# power.net
KiCad netlist of a schematic drawn in Altium Designer
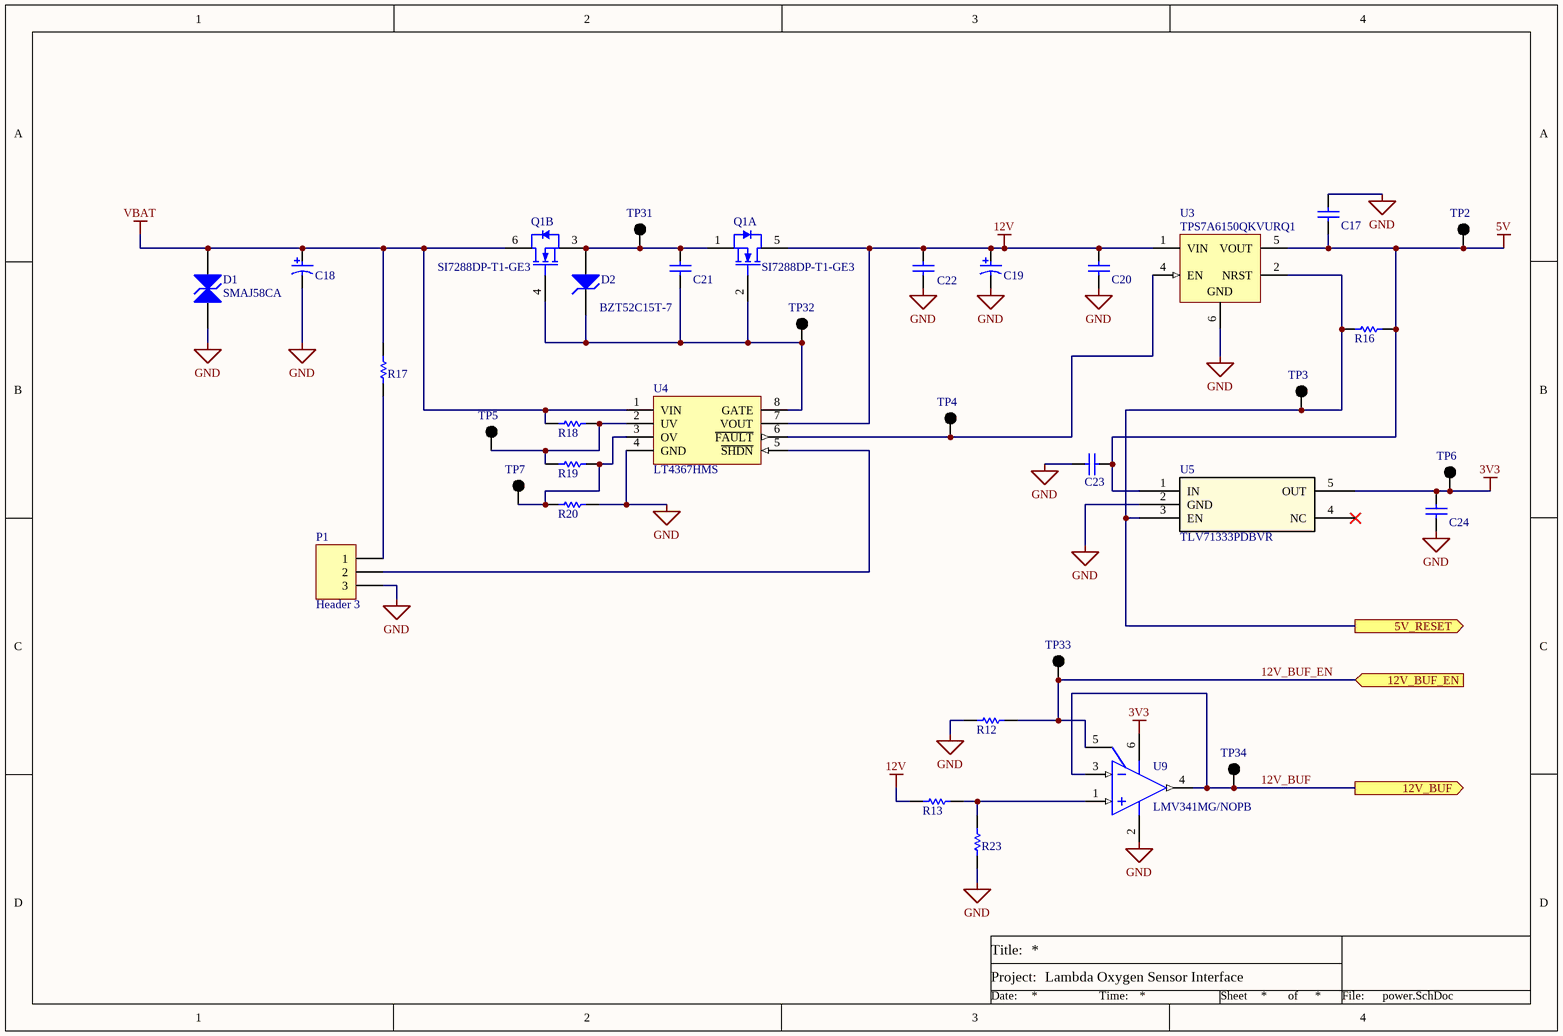
[diagram p0: power.SchDoc]

(export (version "E")
  (design (tool "Eeschema 10.0.6"))
  (components
    (comp (ref "C17")
      (value "Generic 0805 Capacitor")
      (footprint "0805")
      (libsource (lib "symbol_library") (part "C_0805"))
    )
    (comp (ref "C18")
      (value "Generic Electrolytic Capacitor")
      (footprint "NIC-UUX2A470MNL1GS_M")
      (description "Generic PCAP_10x10 Can Aluminum Electrolytic Capacitor")
      (libsource (lib "symbol_library") (part "C_can"))
    )
    (comp (ref "C19")
      (value "Generic Electrolytic Capacitor")
      (footprint "NIC-UUX2A470MNL1GS_M")
      (description "Generic PCAP_10x10 Can Aluminum Electrolytic Capacitor")
      (libsource (lib "symbol_library") (part "C_can"))
    )
    (comp (ref "C20")
      (value "Generic 0805 Capacitor")
      (footprint "0805")
      (libsource (lib "symbol_library") (part "C_0805"))
    )
    (comp (ref "C21")
      (value "Generic 0805 Capacitor")
      (footprint "0805")
      (libsource (lib "symbol_library") (part "C_0805"))
    )
    (comp (ref "C22")
      (value "Generic 0805 Capacitor")
      (footprint "0805")
      (libsource (lib "symbol_library") (part "C_0805"))
    )
    (comp (ref "C23")
      (value "Generic 0805 Capacitor")
      (footprint "0805")
      (libsource (lib "symbol_library") (part "C_0805"))
    )
    (comp (ref "C24")
      (value "Generic 0805 Capacitor")
      (footprint "0805")
      (libsource (lib "symbol_library") (part "C_0805"))
    )
    (comp (ref "D1")
      (value "SMAJ58CA")
      (footprint "VISH-DO-214AC-2_M")
      (fields
        (field (name "MANUFACTURER") "Vishay Semiconductor")
        (field (name "PARTNUMBER") "SMAJ58CA-E3/5A")
      )
      (libsource (lib "symbol_library") (part "SMAJ58CA"))
    )
    (comp (ref "D2")
      (value "BZT52C15T-7")
      (footprint "DIOD-SOD123-2_V")
      (description "Zener Diode 15V 300mW ±6% Surface Mount SOD-523")
      (fields (field (name "MANUFACTURER") "Diodes Inc") (field (name "PARTNUMBER") "BZT52C16-7-F"))
      (libsource (lib "symbol_library") (part "BZT52C15T"))
    )
    (comp (ref "P1")
      (value "Header 3")
      (footprint "HDR1X3")
      (description "Header, 3-Pin")
      (fields (field (name "PUBLISHER") "Altium Limited"))
      (libsource (lib "Miscellaneous Connectors") (part "Header 3"))
    )
    (comp (ref "Q1")
      (value "SI7288DP-T1-GE3")
      (footprint "VISH-POWERPAKSO-8_A_V")
      (description "Dual N-Channel (D-S) MOSFET, 40 V, 20 A, -55 to 150 degC, 8-Pin POWERPAKSO-8, RoHS, Tape and Reel")
      (fields (field (name "MANUFACTURER") "Vishay"))
      (libsource (lib "symbol_library") (part "SI7288DP"))
    )
    (comp (ref "R12")
      (value "Generic 0603 Resistor")
      (footprint "0603")
      (libsource (lib "symbol_library") (part "R_0603"))
    )
    (comp (ref "R13")
      (value "Generic 0603 Resistor")
      (footprint "0603")
      (libsource (lib "symbol_library") (part "R_0603"))
    )
    (comp (ref "R16")
      (value "Generic 0603 Resistor")
      (footprint "0603")
      (libsource (lib "symbol_library") (part "R_0603"))
    )
    (comp (ref "R17")
      (value "Generic 0603 Resistor")
      (footprint "0603")
      (libsource (lib "symbol_library") (part "R_0603"))
    )
    (comp (ref "R18")
      (value "Generic 0603 Resistor")
      (footprint "0603")
      (libsource (lib "symbol_library") (part "R_0603"))
    )
    (comp (ref "R19")
      (value "Generic 0603 Resistor")
      (footprint "0603")
      (libsource (lib "symbol_library") (part "R_0603"))
    )
    (comp (ref "R20")
      (value "Generic 0603 Resistor")
      (footprint "0603")
      (libsource (lib "symbol_library") (part "R_0603"))
    )
    (comp (ref "R23")
      (value "Generic 0603 Resistor")
      (footprint "0603")
      (libsource (lib "symbol_library") (part "R_0603"))
    )
    (comp (ref "TP2")
      (value "5001")
      (footprint "KSTN-5001")
      (description "Test Point, Black, 1-Pin THD, RoHS, Bulk")
      (fields (field (name "MANUFACTURER") "Keystone"))
      (libsource (lib "symbol_library") (part "TP5001"))
    )
    (comp (ref "TP3")
      (value "5001")
      (footprint "KSTN-5001")
      (description "Test Point, Black, 1-Pin THD, RoHS, Bulk")
      (fields (field (name "MANUFACTURER") "Keystone"))
      (libsource (lib "symbol_library") (part "TP5001"))
    )
    (comp (ref "TP4")
      (value "5001")
      (footprint "KSTN-5001")
      (description "Test Point, Black, 1-Pin THD, RoHS, Bulk")
      (fields (field (name "MANUFACTURER") "Keystone"))
      (libsource (lib "symbol_library") (part "TP5001"))
    )
    (comp (ref "TP5")
      (value "5001")
      (footprint "KSTN-5001")
      (description "Test Point, Black, 1-Pin THD, RoHS, Bulk")
      (fields (field (name "MANUFACTURER") "Keystone"))
      (libsource (lib "symbol_library") (part "TP5001"))
    )
    (comp (ref "TP6")
      (value "5001")
      (footprint "KSTN-5001")
      (description "Test Point, Black, 1-Pin THD, RoHS, Bulk")
      (fields (field (name "MANUFACTURER") "Keystone"))
      (libsource (lib "symbol_library") (part "TP5001"))
    )
    (comp (ref "TP7")
      (value "5001")
      (footprint "KSTN-5001")
      (description "Test Point, Black, 1-Pin THD, RoHS, Bulk")
      (fields (field (name "MANUFACTURER") "Keystone"))
      (libsource (lib "symbol_library") (part "TP5001"))
    )
    (comp (ref "TP31")
      (value "5001")
      (footprint "KSTN-5001")
      (description "Test Point, Black, 1-Pin THD, RoHS, Bulk")
      (fields (field (name "MANUFACTURER") "Keystone"))
      (libsource (lib "symbol_library") (part "TP5001"))
    )
    (comp (ref "TP32")
      (value "5001")
      (footprint "KSTN-5001")
      (description "Test Point, Black, 1-Pin THD, RoHS, Bulk")
      (fields (field (name "MANUFACTURER") "Keystone"))
      (libsource (lib "symbol_library") (part "TP5001"))
    )
    (comp (ref "TP33")
      (value "5001")
      (footprint "KSTN-5001")
      (description "Test Point, Black, 1-Pin THD, RoHS, Bulk")
      (fields (field (name "MANUFACTURER") "Keystone"))
      (libsource (lib "symbol_library") (part "TP5001"))
    )
    (comp (ref "TP34")
      (value "5001")
      (footprint "KSTN-5001")
      (description "Test Point, Black, 1-Pin THD, RoHS, Bulk")
      (fields (field (name "MANUFACTURER") "Keystone"))
      (libsource (lib "symbol_library") (part "TP5001"))
    )
    (comp (ref "U3")
      (value "TPS7A6150QKVURQ1")
      (footprint "KVU0005A_M")
      (fields (field (name "MANUFACTURER") "Texas Instruments"))
      (libsource (lib "symbol_library") (part "TPS7A6150-Q1"))
    )
    (comp (ref "U4")
      (value "LT4367HMS")
      (footprint "MSOP8_M")
      (description "100V Overvoltage, Undervoltage and Reverse Supply Protection Controller")
      (libsource (lib "symbol_library") (part "LT4367"))
    )
    (comp (ref "U5")
      (value "TLV71333PDBVR")
      (footprint "DBV5-M")
      (description "REG LINEAR 3.3V 150MA SOT23-5")
      (libsource (lib "symbol_library") (part "TLV71333PDBVR"))
    )
    (comp (ref "U9")
      (value "LMV341MG/NOPB")
      (footprint "DCK0006A_M")
      (fields (field (name "MANUFACTURER") "Texas Instruments"))
      (libsource (lib "symbol_library") (part "LMV341"))
    )
  )
  (nets
    (net (code "1") (name "/5V_RESET") (class "Default")
      (node (ref "R16") (pin "1") (pinfunction "1_1") (pintype "passive"))
      (node (ref "TP3") (pin "1") (pintype "passive"))
      (node (ref "U3") (pin "2") (pinfunction "NRST_2") (pintype "open_collector"))
      (node (ref "U5") (pin "3") (pinfunction "EN_3") (pintype "passive"))
    )
    (net (code "2") (name "/12V_BUF") (class "Default")
      (node (ref "TP34") (pin "1") (pintype "passive"))
      (node (ref "U9") (pin "3") (pinfunction "IN-_3") (pintype "input"))
      (node (ref "U9") (pin "4") (pinfunction "OUT_4") (pintype "output"))
    )
    (net (code "3") (name "/12V_BUF_EN") (class "Default")
      (node (ref "R12") (pin "1") (pinfunction "1_1") (pintype "passive"))
      (node (ref "TP33") (pin "1") (pintype "passive"))
      (node (ref "U9") (pin "5") (pinfunction "~{SHDN}_5") (pintype "passive"))
    )
    (net (code "4") (name "3V3") (class "Default")
      (node (ref "C24") (pin "2") (pinfunction "2_2") (pintype "passive"))
      (node (ref "TP6") (pin "1") (pintype "passive"))
      (node (ref "U5") (pin "5") (pinfunction "OUT_5") (pintype "passive"))
      (node (ref "U9") (pin "6") (pinfunction "V+_6") (pintype "power_in"))
    )
    (net (code "5") (name "5V") (class "Default")
      (node (ref "C17") (pin "1") (pinfunction "1_1") (pintype "passive"))
      (node (ref "C23") (pin "2") (pinfunction "2_2") (pintype "passive"))
      (node (ref "R16") (pin "2") (pinfunction "2_2") (pintype "passive"))
      (node (ref "TP2") (pin "1") (pintype "passive"))
      (node (ref "U3") (pin "5") (pinfunction "VOUT_5") (pintype "power_in"))
      (node (ref "U5") (pin "1") (pinfunction "IN_1") (pintype "passive"))
    )
    (net (code "6") (name "12V") (class "Default")
      (node (ref "C19") (pin "1") (pinfunction "1_1") (pintype "passive"))
      (node (ref "C20") (pin "2") (pinfunction "2_2") (pintype "passive"))
      (node (ref "C22") (pin "2") (pinfunction "2_2") (pintype "passive"))
      (node (ref "Q1") (pin "5") (pinfunction "G2_5") (pintype "passive"))
      (node (ref "R13") (pin "1") (pinfunction "1_1") (pintype "passive"))
      (node (ref "U3") (pin "1") (pinfunction "VIN_1") (pintype "power_in"))
      (node (ref "U4") (pin "7") (pinfunction "VOUT_7") (pintype "passive"))
    )
    (net (code "7") (name "GND") (class "Default")
      (node (ref "C17") (pin "2") (pinfunction "2_2") (pintype "passive"))
      (node (ref "C18") (pin "2") (pinfunction "2_2") (pintype "passive"))
      (node (ref "C19") (pin "2") (pinfunction "2_2") (pintype "passive"))
      (node (ref "C20") (pin "1") (pinfunction "1_1") (pintype "passive"))
      (node (ref "C22") (pin "1") (pinfunction "1_1") (pintype "passive"))
      (node (ref "C23") (pin "1") (pinfunction "1_1") (pintype "passive"))
      (node (ref "C24") (pin "1") (pinfunction "1_1") (pintype "passive"))
      (node (ref "D1") (pin "1") (pinfunction "A1_1") (pintype "passive"))
      (node (ref "P1") (pin "3") (pinfunction "3_3") (pintype "passive"))
      (node (ref "R12") (pin "2") (pinfunction "2_2") (pintype "passive"))
      (node (ref "R20") (pin "2") (pinfunction "2_2") (pintype "passive"))
      (node (ref "R23") (pin "1") (pinfunction "1_1") (pintype "passive"))
      (node (ref "U3") (pin "6") (pinfunction "GND_6") (pintype "power_in"))
      (node (ref "U4") (pin "4") (pinfunction "GND_4") (pintype "power_in"))
      (node (ref "U5") (pin "2") (pinfunction "GND_2") (pintype "power_in"))
      (node (ref "U9") (pin "2") (pinfunction "GND_2") (pintype "power_in"))
    )
    (net (code "8") (name "Net-(D2-A)") (class "Default")
      (node (ref "C21") (pin "2") (pinfunction "2_2") (pintype "passive"))
      (node (ref "D2") (pin "1") (pinfunction "A_1") (pintype "passive"))
      (node (ref "Q1") (pin "1") (pinfunction "S2_1") (pintype "passive"))
      (node (ref "Q1") (pin "3") (pinfunction "S2_3") (pintype "passive"))
      (node (ref "TP31") (pin "1") (pintype "passive"))
    )
    (net (code "9") (name "Net-(D2-K)") (class "Default")
      (node (ref "C21") (pin "1") (pinfunction "1_1") (pintype "passive"))
      (node (ref "D2") (pin "2") (pinfunction "K_2") (pintype "passive"))
      (node (ref "Q1") (pin "2") (pinfunction "G2_2") (pintype "passive"))
      (node (ref "Q1") (pin "4") (pinfunction "G2_4") (pintype "passive"))
      (node (ref "TP32") (pin "1") (pintype "passive"))
      (node (ref "U4") (pin "8") (pinfunction "GATE_8") (pintype "passive"))
    )
    (net (code "10") (name "Net-(P1-Pad1)") (class "Default")
      (node (ref "P1") (pin "1") (pinfunction "1_1") (pintype "passive"))
      (node (ref "R17") (pin "1") (pinfunction "1_1") (pintype "passive"))
    )
    (net (code "11") (name "Net-(U3-EN)") (class "Default")
      (node (ref "TP4") (pin "1") (pintype "passive"))
      (node (ref "U3") (pin "4") (pinfunction "EN_4") (pintype "input"))
      (node (ref "U4") (pin "6") (pinfunction "~{FAULT}_6") (pintype "output"))
    )
    (net (code "12") (name "Net-(U4-OV)") (class "Default")
      (node (ref "R19") (pin "2") (pinfunction "2_2") (pintype "passive"))
      (node (ref "R20") (pin "1") (pinfunction "1_1") (pintype "passive"))
      (node (ref "TP7") (pin "1") (pintype "passive"))
      (node (ref "U4") (pin "3") (pinfunction "OV_3") (pintype "passive"))
    )
    (net (code "13") (name "Net-(U4-UV)") (class "Default")
      (node (ref "R18") (pin "2") (pinfunction "2_2") (pintype "passive"))
      (node (ref "R19") (pin "1") (pinfunction "1_1") (pintype "passive"))
      (node (ref "TP5") (pin "1") (pintype "passive"))
      (node (ref "U4") (pin "2") (pinfunction "UV_2") (pintype "passive"))
    )
    (net (code "14") (name "Net-(U4-~{SHDN})") (class "Default")
      (node (ref "P1") (pin "2") (pinfunction "2_2") (pintype "passive"))
      (node (ref "U4") (pin "5") (pinfunction "~{SHDN}_5") (pintype "input"))
    )
    (net (code "15") (name "Net-(U9-IN+)") (class "Default")
      (node (ref "R13") (pin "2") (pinfunction "2_2") (pintype "passive"))
      (node (ref "R23") (pin "2") (pinfunction "2_2") (pintype "passive"))
      (node (ref "U9") (pin "1") (pinfunction "IN+_1") (pintype "input"))
    )
    (net (code "16") (name "VBAT") (class "Default")
      (node (ref "C18") (pin "1") (pinfunction "1_1") (pintype "passive"))
      (node (ref "D1") (pin "2") (pinfunction "A2_2") (pintype "passive"))
      (node (ref "Q1") (pin "6") (pinfunction "G2_6") (pintype "passive"))
      (node (ref "R17") (pin "2") (pinfunction "2_2") (pintype "passive"))
      (node (ref "R18") (pin "1") (pinfunction "1_1") (pintype "passive"))
      (node (ref "U4") (pin "1") (pinfunction "VIN_1") (pintype "power_in"))
    )
    (net (code "17") (name "unconnected-(U5-NC-Pad4)") (class "Default")
      (node (ref "U5") (pin "4") (pinfunction "NC_4") (pintype "passive+no_connect"))
    )
  )
)
